# Modem_GNSS.net
KiCad netlist of a schematic drawn in Altium Designer
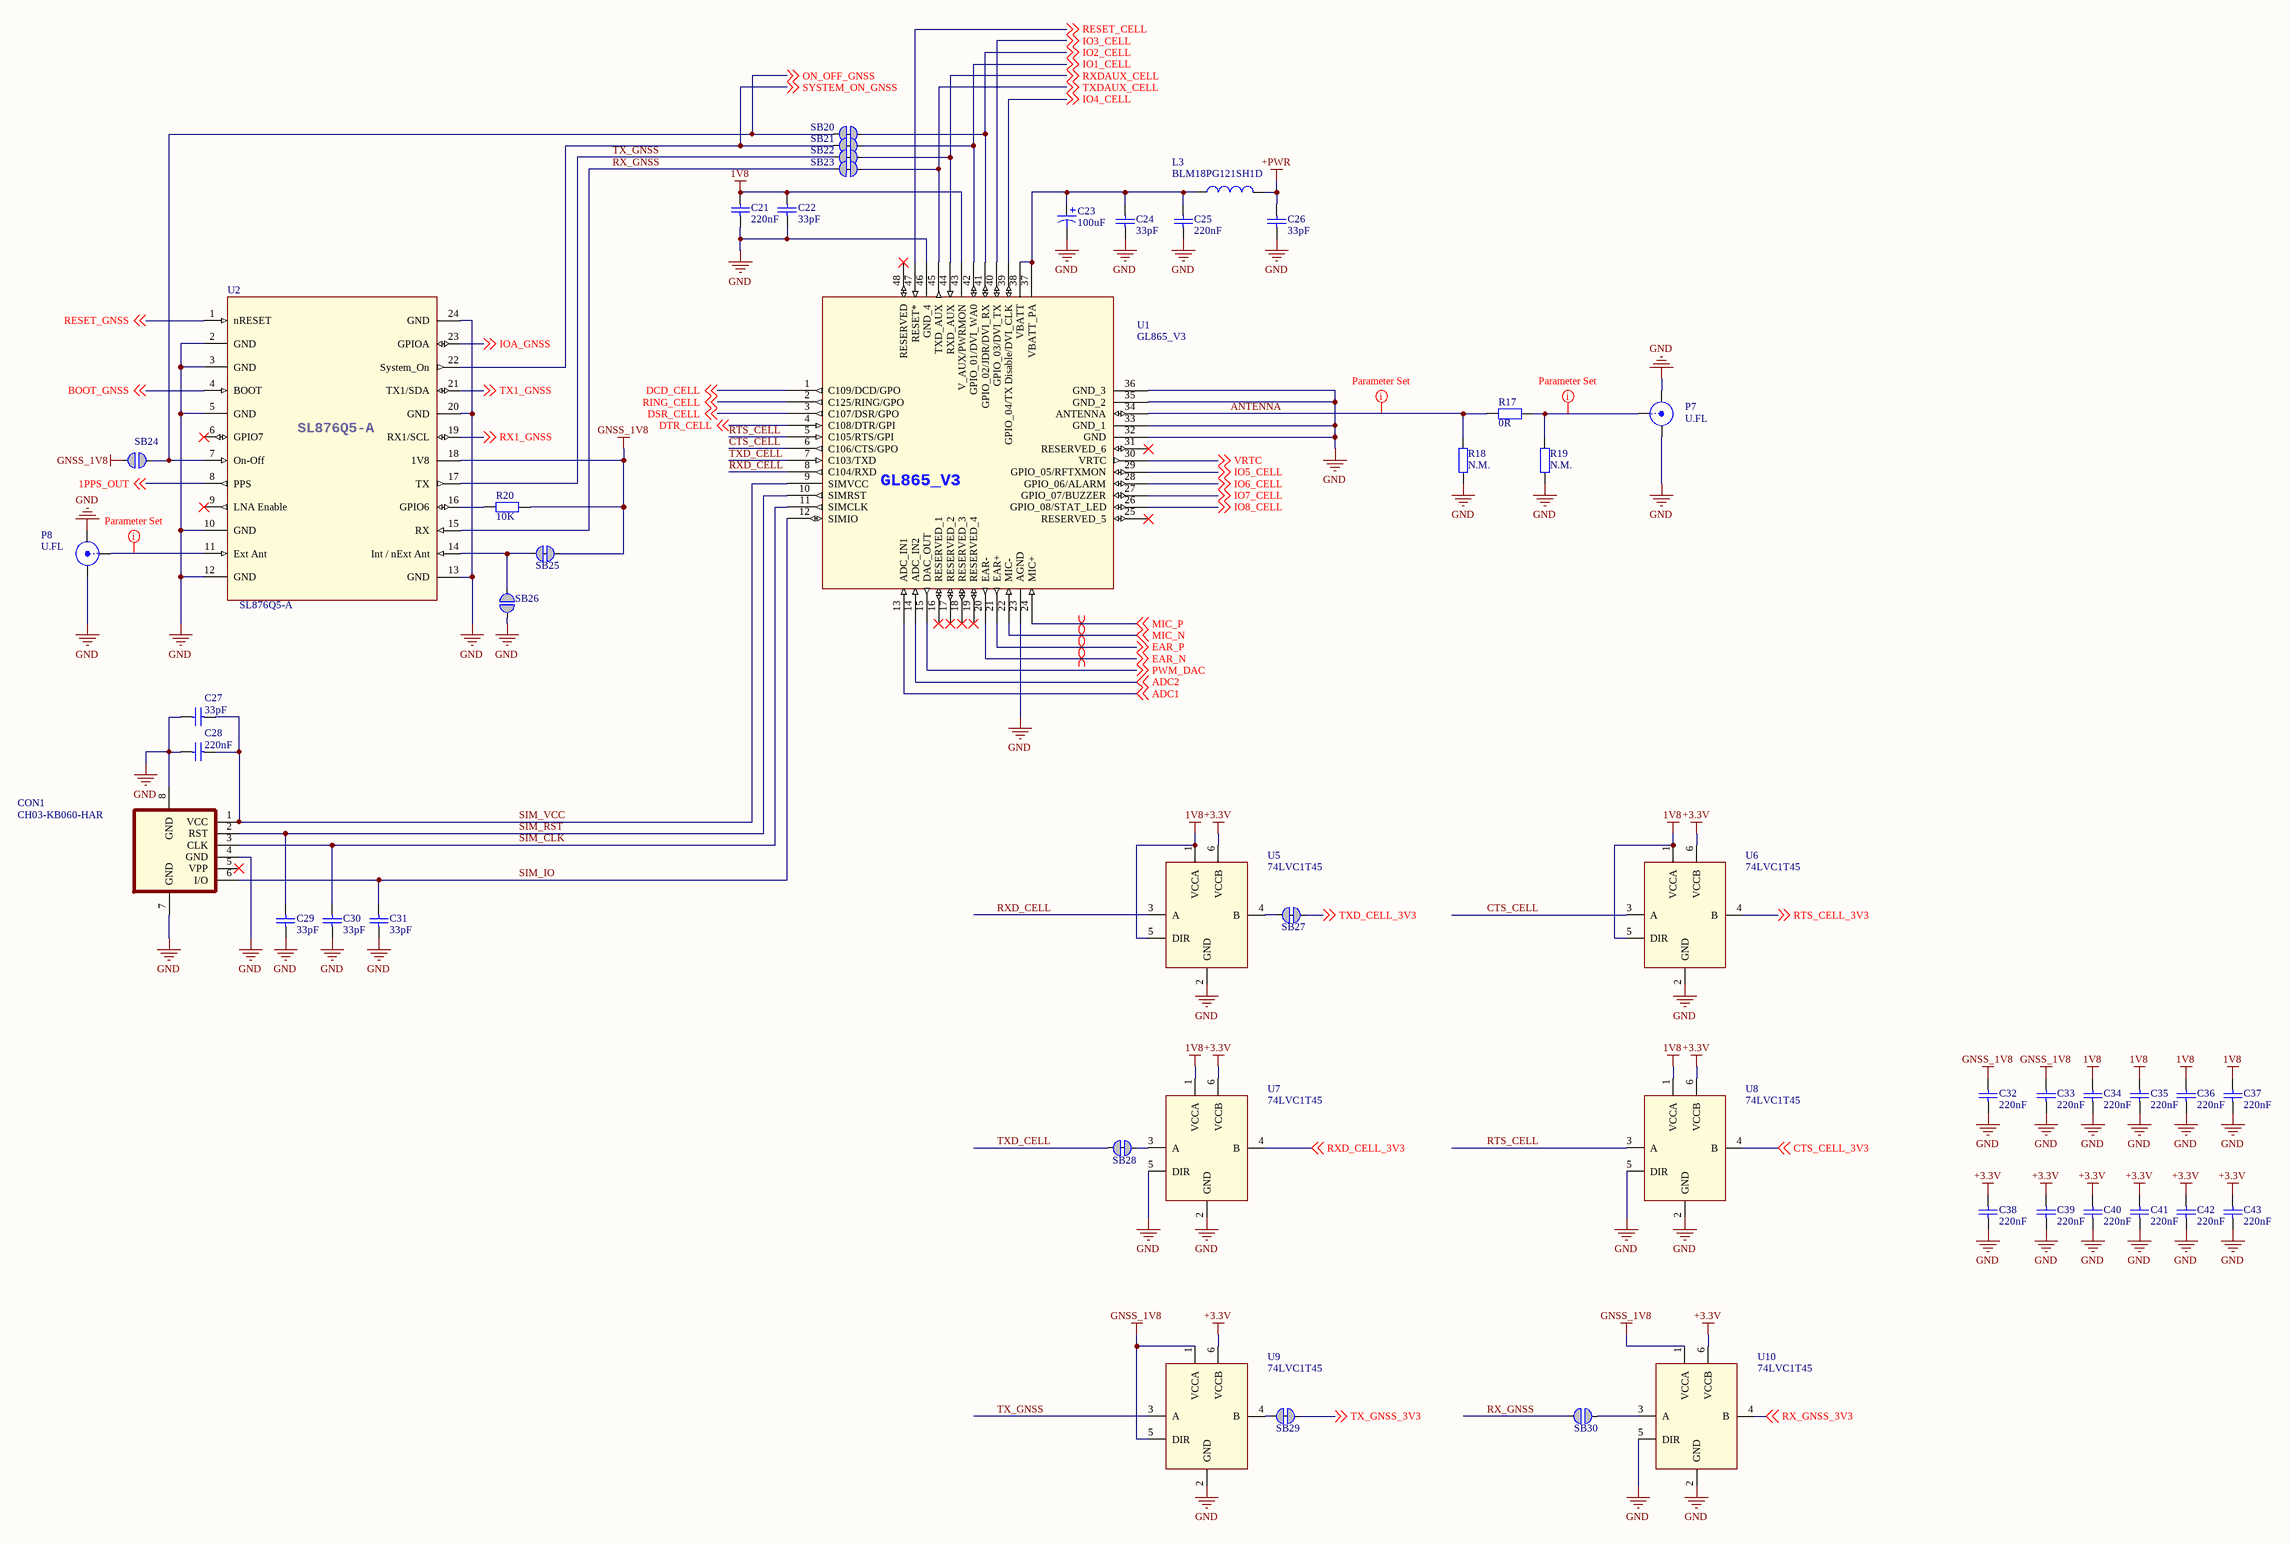
[diagram p0: Modem GNSS.SchDoc]

(export (version "E")
  (design (tool "Eeschema 10.0.6"))
  (components
    (comp (ref "C21")
      (value "220nF")
      (footprint "C0402")
      (description "Capacitor (Semiconductor SIM Model)")
      (fields
        (field (name "MANUFACTURER") "YAGEO")
        (field (name "MANUFACTURER PART NO.") "CC0402KRX5R5BB224")
      )
      (libsource (lib "Miscellaneous Devices") (part "Cap Semi"))
    )
    (comp (ref "C22")
      (value "33pF")
      (footprint "C0402")
      (description "Capacitor (Semiconductor SIM Model)")
      (fields (field (name "MANUFACTURER") "AVX") (field (name "MANUFACTURER PART NO.") "04025A330JAT2A"))
      (libsource (lib "Miscellaneous Devices") (part "Cap Semi"))
    )
    (comp (ref "C23")
      (value "100uF")
      (footprint "Case-B")
      (fields
        (field (name "MANUFACTURER") "AVX")
        (field (name "MANUFACTURER PART NO.") "TPSB107K006R0400")
        (field (name "Comment") "electrolytic capacitor")
      )
      (libsource (lib "Miscellaneous Devices") (part "Cap Pol1"))
    )
    (comp (ref "C24")
      (value "33pF")
      (footprint "C0402")
      (description "Capacitor (Semiconductor SIM Model)")
      (fields (field (name "MANUFACTURER") "AVX") (field (name "MANUFACTURER PART NO.") "04025A330JAT2A"))
      (libsource (lib "Miscellaneous Devices") (part "Cap Semi"))
    )
    (comp (ref "C25")
      (value "220nF")
      (footprint "C0402")
      (description "Capacitor (Semiconductor SIM Model)")
      (fields
        (field (name "MANUFACTURER") "YAGEO")
        (field (name "MANUFACTURER PART NO.") "CC0402KRX5R5BB224")
      )
      (libsource (lib "Miscellaneous Devices") (part "Cap Semi"))
    )
    (comp (ref "C26")
      (value "33pF")
      (footprint "C0402")
      (description "Capacitor (Semiconductor SIM Model)")
      (fields (field (name "MANUFACTURER") "AVX") (field (name "MANUFACTURER PART NO.") "04025A330JAT2A"))
      (libsource (lib "Miscellaneous Devices") (part "Cap Semi"))
    )
    (comp (ref "C27")
      (value "33pF")
      (footprint "C0402")
      (description "Capacitor (Semiconductor SIM Model)")
      (fields (field (name "MANUFACTURER") "AVX") (field (name "MANUFACTURER PART NO.") "04025A330JAT2A"))
      (libsource (lib "Miscellaneous Devices") (part "Cap Semi"))
    )
    (comp (ref "C28")
      (value "220nF")
      (footprint "C0402")
      (description "Capacitor (Semiconductor SIM Model)")
      (fields
        (field (name "MANUFACTURER") "YAGEO")
        (field (name "MANUFACTURER PART NO.") "CC0402KRX5R5BB224")
      )
      (libsource (lib "Miscellaneous Devices") (part "Cap Semi"))
    )
    (comp (ref "C29")
      (value "33pF")
      (footprint "C0402")
      (description "Capacitor (Semiconductor SIM Model)")
      (fields (field (name "MANUFACTURER") "AVX") (field (name "MANUFACTURER PART NO.") "04025A330JAT2A"))
      (libsource (lib "Miscellaneous Devices") (part "Cap Semi"))
    )
    (comp (ref "C30")
      (value "33pF")
      (footprint "C0402")
      (description "Capacitor (Semiconductor SIM Model)")
      (fields (field (name "MANUFACTURER") "AVX") (field (name "MANUFACTURER PART NO.") "04025A330JAT2A"))
      (libsource (lib "Miscellaneous Devices") (part "Cap Semi"))
    )
    (comp (ref "C31")
      (value "33pF")
      (footprint "C0402")
      (description "Capacitor (Semiconductor SIM Model)")
      (fields (field (name "MANUFACTURER") "AVX") (field (name "MANUFACTURER PART NO.") "04025A330JAT2A"))
      (libsource (lib "Miscellaneous Devices") (part "Cap Semi"))
    )
    (comp (ref "C32")
      (value "220nF")
      (footprint "C0402")
      (description "Capacitor (Semiconductor SIM Model)")
      (fields
        (field (name "MANUFACTURER") "YAGEO")
        (field (name "MANUFACTURER PART NO.") "CC0402KRX5R5BB224")
      )
      (libsource (lib "Miscellaneous Devices") (part "Cap Semi"))
    )
    (comp (ref "C33")
      (value "220nF")
      (footprint "C0402")
      (description "Capacitor (Semiconductor SIM Model)")
      (fields
        (field (name "MANUFACTURER") "YAGEO")
        (field (name "MANUFACTURER PART NO.") "CC0402KRX5R5BB224")
      )
      (libsource (lib "Miscellaneous Devices") (part "Cap Semi"))
    )
    (comp (ref "C34")
      (value "220nF")
      (footprint "C0402")
      (description "Capacitor (Semiconductor SIM Model)")
      (fields
        (field (name "MANUFACTURER") "YAGEO")
        (field (name "MANUFACTURER PART NO.") "CC0402KRX5R5BB224")
      )
      (libsource (lib "Miscellaneous Devices") (part "Cap Semi"))
    )
    (comp (ref "C35")
      (value "220nF")
      (footprint "C0402")
      (description "Capacitor (Semiconductor SIM Model)")
      (fields
        (field (name "MANUFACTURER") "YAGEO")
        (field (name "MANUFACTURER PART NO.") "CC0402KRX5R5BB224")
      )
      (libsource (lib "Miscellaneous Devices") (part "Cap Semi"))
    )
    (comp (ref "C36")
      (value "220nF")
      (footprint "C0402")
      (description "Capacitor (Semiconductor SIM Model)")
      (fields
        (field (name "MANUFACTURER") "YAGEO")
        (field (name "MANUFACTURER PART NO.") "CC0402KRX5R5BB224")
      )
      (libsource (lib "Miscellaneous Devices") (part "Cap Semi"))
    )
    (comp (ref "C37")
      (value "220nF")
      (footprint "C0402")
      (description "Capacitor (Semiconductor SIM Model)")
      (fields
        (field (name "MANUFACTURER") "YAGEO")
        (field (name "MANUFACTURER PART NO.") "CC0402KRX5R5BB224")
      )
      (libsource (lib "Miscellaneous Devices") (part "Cap Semi"))
    )
    (comp (ref "C38")
      (value "220nF")
      (footprint "C0402")
      (description "Capacitor (Semiconductor SIM Model)")
      (fields
        (field (name "MANUFACTURER") "YAGEO")
        (field (name "MANUFACTURER PART NO.") "CC0402KRX5R5BB224")
      )
      (libsource (lib "Miscellaneous Devices") (part "Cap Semi"))
    )
    (comp (ref "C39")
      (value "220nF")
      (footprint "C0402")
      (description "Capacitor (Semiconductor SIM Model)")
      (fields
        (field (name "MANUFACTURER") "YAGEO")
        (field (name "MANUFACTURER PART NO.") "CC0402KRX5R5BB224")
      )
      (libsource (lib "Miscellaneous Devices") (part "Cap Semi"))
    )
    (comp (ref "C40")
      (value "220nF")
      (footprint "C0402")
      (description "Capacitor (Semiconductor SIM Model)")
      (fields
        (field (name "MANUFACTURER") "YAGEO")
        (field (name "MANUFACTURER PART NO.") "CC0402KRX5R5BB224")
      )
      (libsource (lib "Miscellaneous Devices") (part "Cap Semi"))
    )
    (comp (ref "C41")
      (value "220nF")
      (footprint "C0402")
      (description "Capacitor (Semiconductor SIM Model)")
      (fields
        (field (name "MANUFACTURER") "YAGEO")
        (field (name "MANUFACTURER PART NO.") "CC0402KRX5R5BB224")
      )
      (libsource (lib "Miscellaneous Devices") (part "Cap Semi"))
    )
    (comp (ref "C42")
      (value "220nF")
      (footprint "C0402")
      (description "Capacitor (Semiconductor SIM Model)")
      (fields
        (field (name "MANUFACTURER") "YAGEO")
        (field (name "MANUFACTURER PART NO.") "CC0402KRX5R5BB224")
      )
      (libsource (lib "Miscellaneous Devices") (part "Cap Semi"))
    )
    (comp (ref "C43")
      (value "220nF")
      (footprint "C0402")
      (description "Capacitor (Semiconductor SIM Model)")
      (fields
        (field (name "MANUFACTURER") "YAGEO")
        (field (name "MANUFACTURER PART NO.") "CC0402KRX5R5BB224")
      )
      (libsource (lib "Miscellaneous Devices") (part "Cap Semi"))
    )
    (comp (ref "CON1")
      (value "CH03-KB060-HAR")
      (footprint "CH03-KB")
      (description "Nano SIM Card Connector")
      (fields (field (name "MANUFACTURER") "GradConn"))
      (libsource (lib "CH03-KB060-HAR") (part "CH03-KB060-HAR"))
    )
    (comp (ref "L3")
      (value "BLM18PG121SH1D")
      (footprint "L0603")
      (description "Inductor")
      (fields (field (name "MANUFACTURER") "muRata"))
      (libsource (lib "Miscellaneous Devices") (part "Inductor"))
    )
    (comp (ref "P7")
      (value "U.FL")
      (footprint "U.FL_Connector_Male")
      (fields
        (field (name "MANUFACTURER") "HIROSE")
        (field (name "MANUFACTURER PART NO.") "U.FL-R-SMT-1(10)")
      )
      (libsource (lib "RUT_L865_Project_1") (part "SMB"))
    )
    (comp (ref "P8")
      (value "U.FL")
      (footprint "U.FL_Connector_Male")
      (fields
        (field (name "MANUFACTURER") "HIROSE")
        (field (name "MANUFACTURER PART NO.") "U.FL-R-SMT-1(10)")
      )
      (libsource (lib "RUT_L865_Project_1") (part "SMB"))
    )
    (comp (ref "R17")
      (value "0R")
      (footprint "R0402")
      (fields
        (field (name "MANUFACTURER") "YAGEO")
        (field (name "MANUFACTURER PART NO.") "RC0402FR-070RL")
        (field (name "Comment") "Res2")
      )
      (libsource (lib "") (part "Res2_1"))
    )
    (comp (ref "R18")
      (value "N.M.")
      (footprint "R0402")
      (fields
        (field (name "MANUFACTURER") "YAGEO")
        (field (name "MANUFACTURER PART NO.") "RC0402FR-070RL")
        (field (name "Comment") "Res2")
      )
      (libsource (lib "") (part "Res2_2"))
    )
    (comp (ref "R19")
      (value "N.M.")
      (footprint "R0402")
      (fields
        (field (name "MANUFACTURER") "YAGEO")
        (field (name "MANUFACTURER PART NO.") "RC0402FR-070RL")
        (field (name "Comment") "Res2")
      )
      (libsource (lib "") (part "Res2_2"))
    )
    (comp (ref "R20")
      (value "10K")
      (footprint "R0402")
      (fields
        (field (name "MANUFACTURER") "ASJ")
        (field (name "MANUFACTURER PART NO.") "CR10-103-JK")
        (field (name "Comment") "Res2")
      )
      (libsource (lib "Miscellaneous Devices") (part "Res2"))
    )
    (comp (ref "SB20")
      (value "Solderbridge")
      (footprint "Solderbridge_Shorted")
      (libsource (lib "altium-import") (part "root_0_SOLDERBRIDGE_SHORTED_"))
    )
    (comp (ref "SB21")
      (value "Solderbridge")
      (footprint "Solderbridge_Shorted")
      (libsource (lib "altium-import") (part "root_0_SOLDERBRIDGE_SHORTED_"))
    )
    (comp (ref "SB22")
      (value "Solderbridge")
      (footprint "Solderbridge_Shorted")
      (libsource (lib "altium-import") (part "root_0_SOLDERBRIDGE_SHORTED_"))
    )
    (comp (ref "SB23")
      (value "Solderbridge")
      (footprint "Solderbridge_Shorted")
      (libsource (lib "altium-import") (part "root_0_SOLDERBRIDGE_SHORTED_"))
    )
    (comp (ref "SB24")
      (value "Solderbridge")
      (footprint "Solderbridge")
      (libsource (lib "altium-import") (part "root_0_SOLDERBRIDGE_"))
    )
    (comp (ref "SB25")
      (value "Solderbridge")
      (footprint "Solderbridge_Shorted")
      (libsource (lib "altium-import") (part "root_0_SOLDERBRIDGE_SHORTED_"))
    )
    (comp (ref "SB26")
      (value "Solderbridge")
      (footprint "Solderbridge")
      (libsource (lib "altium-import") (part "root_3_SOLDERBRIDGE_"))
    )
    (comp (ref "SB27")
      (value "Solderbridge")
      (footprint "Solderbridge_Shorted")
      (libsource (lib "altium-import") (part "root_0_SOLDERBRIDGE_SHORTED_"))
    )
    (comp (ref "SB28")
      (value "Solderbridge")
      (footprint "Solderbridge_Shorted")
      (libsource (lib "altium-import") (part "root_2_SOLDERBRIDGE_SHORTED_"))
    )
    (comp (ref "SB29")
      (value "Solderbridge")
      (footprint "Solderbridge_Shorted")
      (libsource (lib "altium-import") (part "root_2_SOLDERBRIDGE_SHORTED_"))
    )
    (comp (ref "SB30")
      (value "Solderbridge")
      (footprint "Solderbridge")
      (libsource (lib "altium-import") (part "root_0_SOLDERBRIDGE_"))
    )
    (comp (ref "U1")
      (value "GL865_V3")
      (footprint "XL865XXX")
      (fields (field (name "MANUFACTURER") "Telit") (field (name "MANUFACTURER PART NO.") "GL865-DUAL V3.1"))
      (libsource (lib "RUT_L865_Project_1") (part "GL865_V3"))
    )
    (comp (ref "U2")
      (value "SL876Q5-A")
      (footprint "SL876Q5-A")
      (fields (field (name "MANUFACTURER") "Telit"))
      (libsource (lib "SL876-Q5A") (part "SL876Q5-A"))
    )
    (comp (ref "U5")
      (value "74LVC1T45")
      (footprint "X2-DFN1410-6")
      (fields
        (field (name "MANUFACTURER") "Diodes Inc.")
        (field (name "MANUFACTURER PART NO.") "74LVC1T45FZ4-7")
      )
      (libsource (lib "74LVC1T45") (part "74LVC1T45"))
    )
    (comp (ref "U6")
      (value "74LVC1T45")
      (footprint "X2-DFN1410-6")
      (fields
        (field (name "MANUFACTURER") "Diodes Inc.")
        (field (name "MANUFACTURER PART NO.") "74LVC1T45FZ4-7")
      )
      (libsource (lib "74LVC1T45") (part "74LVC1T45"))
    )
    (comp (ref "U7")
      (value "74LVC1T45")
      (footprint "X2-DFN1410-6")
      (fields
        (field (name "MANUFACTURER") "Diodes Inc.")
        (field (name "MANUFACTURER PART NO.") "74LVC1T45FZ4-7")
      )
      (libsource (lib "74LVC1T45") (part "74LVC1T45"))
    )
    (comp (ref "U8")
      (value "74LVC1T45")
      (footprint "X2-DFN1410-6")
      (fields
        (field (name "MANUFACTURER") "Diodes Inc.")
        (field (name "MANUFACTURER PART NO.") "74LVC1T45FZ4-7")
      )
      (libsource (lib "74LVC1T45") (part "74LVC1T45"))
    )
    (comp (ref "U9")
      (value "74LVC1T45")
      (footprint "X2-DFN1410-6")
      (fields
        (field (name "MANUFACTURER") "Diodes Inc.")
        (field (name "MANUFACTURER PART NO.") "74LVC1T45FZ4-7")
      )
      (libsource (lib "74LVC1T45") (part "74LVC1T45"))
    )
    (comp (ref "U10")
      (value "74LVC1T45")
      (footprint "X2-DFN1410-6")
      (fields
        (field (name "MANUFACTURER") "Diodes Inc.")
        (field (name "MANUFACTURER PART NO.") "74LVC1T45FZ4-7")
      )
      (libsource (lib "74LVC1T45") (part "74LVC1T45"))
    )
  )
  (nets
    (net (code "1") (name "+3.3V") (class "Default")
      (node (ref "C38") (pin "1") (pinfunction "1_1") (pintype "passive"))
      (node (ref "C39") (pin "1") (pinfunction "1_1") (pintype "passive"))
      (node (ref "C40") (pin "1") (pinfunction "1_1") (pintype "passive"))
      (node (ref "C41") (pin "1") (pinfunction "1_1") (pintype "passive"))
      (node (ref "C42") (pin "1") (pinfunction "1_1") (pintype "passive"))
      (node (ref "C43") (pin "1") (pinfunction "1_1") (pintype "passive"))
      (node (ref "U10") (pin "6") (pinfunction "VCCB_6") (pintype "passive"))
      (node (ref "U5") (pin "6") (pinfunction "VCCB_6") (pintype "passive"))
      (node (ref "U6") (pin "6") (pinfunction "VCCB_6") (pintype "passive"))
      (node (ref "U7") (pin "6") (pinfunction "VCCB_6") (pintype "passive"))
      (node (ref "U8") (pin "6") (pinfunction "VCCB_6") (pintype "passive"))
      (node (ref "U9") (pin "6") (pinfunction "VCCB_6") (pintype "passive"))
    )
    (net (code "2") (name "+PWR") (class "Default")
      (node (ref "C26") (pin "2") (pinfunction "2_2") (pintype "passive"))
      (node (ref "L3") (pin "2") (pinfunction "2_2") (pintype "passive"))
    )
    (net (code "3") (name "/ANTENNA") (class "Default")
      (node (ref "R17") (pin "2") (pinfunction "2_2") (pintype "passive"))
      (node (ref "R18") (pin "1") (pinfunction "1_1") (pintype "passive"))
      (node (ref "U1") (pin "34") (pinfunction "ANTENNA_34") (pintype "bidirectional"))
    )
    (net (code "4") (name "/CTS_CELL") (class "Default")
      (node (ref "U1") (pin "6") (pinfunction "C106/CTS/GPO_6") (pintype "output"))
      (node (ref "U6") (pin "3") (pinfunction "A_3") (pintype "passive"))
    )
    (net (code "5") (name "/RTS_CELL") (class "Default")
      (node (ref "U1") (pin "5") (pinfunction "C105/RTS/GPI_5") (pintype "input"))
      (node (ref "U8") (pin "3") (pinfunction "A_3") (pintype "passive"))
    )
    (net (code "6") (name "/RXD_CELL") (class "Default")
      (node (ref "U1") (pin "8") (pinfunction "C104/RXD_8") (pintype "output"))
      (node (ref "U5") (pin "3") (pinfunction "A_3") (pintype "passive"))
    )
    (net (code "7") (name "/RX_GNSS") (class "Default")
      (node (ref "SB23") (pin "2") (pinfunction "1_2") (pintype "passive"))
      (node (ref "SB30") (pin "2") (pinfunction "1_2") (pintype "passive"))
      (node (ref "U2") (pin "15") (pinfunction "RX_15") (pintype "input"))
    )
    (net (code "8") (name "/SIM_CLK") (class "Default")
      (node (ref "C30") (pin "1") (pinfunction "1_1") (pintype "passive"))
      (node (ref "CON1") (pin "3") (pinfunction "CLK_3") (pintype "passive"))
      (node (ref "U1") (pin "11") (pinfunction "SIMCLK_11") (pintype "output"))
    )
    (net (code "9") (name "/SIM_IO") (class "Default")
      (node (ref "C31") (pin "1") (pinfunction "1_1") (pintype "passive"))
      (node (ref "CON1") (pin "6") (pinfunction "I/O_6") (pintype "passive"))
      (node (ref "U1") (pin "12") (pinfunction "SIMIO_12") (pintype "bidirectional"))
    )
    (net (code "10") (name "/SIM_RST") (class "Default")
      (node (ref "C29") (pin "1") (pinfunction "1_1") (pintype "passive"))
      (node (ref "CON1") (pin "2") (pinfunction "RST_2") (pintype "passive"))
      (node (ref "U1") (pin "10") (pinfunction "SIMRST_10") (pintype "output"))
    )
    (net (code "11") (name "/SIM_VCC") (class "Default")
      (node (ref "C27") (pin "1") (pinfunction "1_1") (pintype "passive"))
      (node (ref "C28") (pin "1") (pinfunction "1_1") (pintype "passive"))
      (node (ref "CON1") (pin "1") (pinfunction "VCC_1") (pintype "passive"))
      (node (ref "U1") (pin "9") (pinfunction "SIMVCC_9") (pintype "power_in"))
    )
    (net (code "12") (name "/TXD_CELL") (class "Default")
      (node (ref "SB28") (pin "1") (pinfunction "0_1") (pintype "passive"))
      (node (ref "U1") (pin "7") (pinfunction "C103/TXD_7") (pintype "input"))
    )
    (net (code "13") (name "/TX_GNSS") (class "Default")
      (node (ref "SB22") (pin "2") (pinfunction "1_2") (pintype "passive"))
      (node (ref "U2") (pin "17") (pinfunction "TX_17") (pintype "output"))
      (node (ref "U9") (pin "3") (pinfunction "A_3") (pintype "passive"))
    )
    (net (code "14") (name "1PPS_OUT") (class "Default")
      (node (ref "U2") (pin "8") (pinfunction "PPS_8") (pintype "output"))
    )
    (net (code "15") (name "1V8") (class "Default")
      (node (ref "C21") (pin "2") (pinfunction "2_2") (pintype "passive"))
      (node (ref "C22") (pin "2") (pinfunction "2_2") (pintype "passive"))
      (node (ref "C34") (pin "1") (pinfunction "1_1") (pintype "passive"))
      (node (ref "C35") (pin "1") (pinfunction "1_1") (pintype "passive"))
      (node (ref "C36") (pin "1") (pinfunction "1_1") (pintype "passive"))
      (node (ref "C37") (pin "1") (pinfunction "1_1") (pintype "passive"))
      (node (ref "U1") (pin "43") (pinfunction "V_AUX/PWRMON_43") (pintype "power_in"))
      (node (ref "U5") (pin "1") (pinfunction "VCCA_1") (pintype "passive"))
      (node (ref "U5") (pin "5") (pinfunction "DIR_5") (pintype "passive"))
      (node (ref "U6") (pin "1") (pinfunction "VCCA_1") (pintype "passive"))
      (node (ref "U6") (pin "5") (pinfunction "DIR_5") (pintype "passive"))
      (node (ref "U7") (pin "1") (pinfunction "VCCA_1") (pintype "passive"))
      (node (ref "U8") (pin "1") (pinfunction "VCCA_1") (pintype "passive"))
    )
    (net (code "16") (name "ADC1") (class "Default")
      (node (ref "U1") (pin "13") (pinfunction "ADC_IN1_13") (pintype "input"))
    )
    (net (code "17") (name "ADC2") (class "Default")
      (node (ref "U1") (pin "14") (pinfunction "ADC_IN2_14") (pintype "input"))
    )
    (net (code "18") (name "BOOT_GNSS") (class "Default")
      (node (ref "U2") (pin "4") (pinfunction "BOOT_4") (pintype "input"))
    )
    (net (code "19") (name "CTS_CELL_3V3") (class "Default")
      (node (ref "U8") (pin "4") (pinfunction "B_4") (pintype "passive"))
    )
    (net (code "20") (name "DCD_CELL") (class "Default")
      (node (ref "U1") (pin "1") (pinfunction "C109/DCD/GPO_1") (pintype "output"))
    )
    (net (code "21") (name "DSR_CELL") (class "Default")
      (node (ref "U1") (pin "3") (pinfunction "C107/DSR/GPO_3") (pintype "output"))
    )
    (net (code "22") (name "DTR_CELL") (class "Default")
      (node (ref "U1") (pin "4") (pinfunction "C108/DTR/GPI_4") (pintype "input"))
    )
    (net (code "23") (name "EAR_N") (class "Default")
      (node (ref "U1") (pin "20") (pinfunction "EAR-_20") (pintype "output"))
    )
    (net (code "24") (name "EAR_P") (class "Default")
      (node (ref "U1") (pin "21") (pinfunction "EAR+_21") (pintype "output"))
    )
    (net (code "25") (name "GND") (class "Default")
      (node (ref "C21") (pin "1") (pinfunction "1_1") (pintype "passive"))
      (node (ref "C22") (pin "1") (pinfunction "1_1") (pintype "passive"))
      (node (ref "C23") (pin "2") (pinfunction "2_2") (pintype "passive"))
      (node (ref "C24") (pin "1") (pinfunction "1_1") (pintype "passive"))
      (node (ref "C25") (pin "1") (pinfunction "1_1") (pintype "passive"))
      (node (ref "C26") (pin "1") (pinfunction "1_1") (pintype "passive"))
      (node (ref "C27") (pin "2") (pinfunction "2_2") (pintype "passive"))
      (node (ref "C28") (pin "2") (pinfunction "2_2") (pintype "passive"))
      (node (ref "C29") (pin "2") (pinfunction "2_2") (pintype "passive"))
      (node (ref "C30") (pin "2") (pinfunction "2_2") (pintype "passive"))
      (node (ref "C31") (pin "2") (pinfunction "2_2") (pintype "passive"))
      (node (ref "C32") (pin "2") (pinfunction "2_2") (pintype "passive"))
      (node (ref "C33") (pin "2") (pinfunction "2_2") (pintype "passive"))
      (node (ref "C34") (pin "2") (pinfunction "2_2") (pintype "passive"))
      (node (ref "C35") (pin "2") (pinfunction "2_2") (pintype "passive"))
      (node (ref "C36") (pin "2") (pinfunction "2_2") (pintype "passive"))
      (node (ref "C37") (pin "2") (pinfunction "2_2") (pintype "passive"))
      (node (ref "C38") (pin "2") (pinfunction "2_2") (pintype "passive"))
      (node (ref "C39") (pin "2") (pinfunction "2_2") (pintype "passive"))
      (node (ref "C40") (pin "2") (pinfunction "2_2") (pintype "passive"))
      (node (ref "C41") (pin "2") (pinfunction "2_2") (pintype "passive"))
      (node (ref "C42") (pin "2") (pinfunction "2_2") (pintype "passive"))
      (node (ref "C43") (pin "2") (pinfunction "2_2") (pintype "passive"))
      (node (ref "CON1") (pin "4") (pinfunction "GND_4") (pintype "passive"))
      (node (ref "CON1") (pin "7") (pinfunction "GND_7") (pintype "passive"))
      (node (ref "CON1") (pin "8") (pinfunction "GND_8") (pintype "passive"))
      (node (ref "P7") (pin "2") (pinfunction "Y_2") (pintype "passive"))
      (node (ref "P7") (pin "3") (pinfunction "Y_3") (pintype "passive"))
      (node (ref "P8") (pin "2") (pinfunction "Y_2") (pintype "passive"))
      (node (ref "P8") (pin "3") (pinfunction "Y_3") (pintype "passive"))
      (node (ref "R18") (pin "2") (pinfunction "2_2") (pintype "passive"))
      (node (ref "R19") (pin "2") (pinfunction "2_2") (pintype "passive"))
      (node (ref "SB26") (pin "1") (pinfunction "0_1") (pintype "passive"))
      (node (ref "U1") (pin "23") (pinfunction "AGND_23") (pintype "power_in"))
      (node (ref "U1") (pin "32") (pinfunction "GND_32") (pintype "power_in"))
      (node (ref "U1") (pin "33") (pinfunction "GND_1_33") (pintype "power_in"))
      (node (ref "U1") (pin "35") (pinfunction "GND_2_35") (pintype "power_in"))
      (node (ref "U1") (pin "36") (pinfunction "GND_3_36") (pintype "power_in"))
      (node (ref "U1") (pin "46") (pinfunction "GND_4_46") (pintype "power_in"))
      (node (ref "U10") (pin "2") (pinfunction "GND_2") (pintype "passive"))
      (node (ref "U10") (pin "5") (pinfunction "DIR_5") (pintype "passive"))
      (node (ref "U2") (pin "10") (pinfunction "GND_10") (pintype "power_in"))
      (node (ref "U2") (pin "12") (pinfunction "GND_12") (pintype "power_in"))
      (node (ref "U2") (pin "13") (pinfunction "GND_13") (pintype "power_in"))
      (node (ref "U2") (pin "2") (pinfunction "GND_2") (pintype "power_in"))
      (node (ref "U2") (pin "20") (pinfunction "GND_20") (pintype "power_in"))
      (node (ref "U2") (pin "24") (pinfunction "GND_24") (pintype "power_in"))
      (node (ref "U2") (pin "3") (pinfunction "GND_3") (pintype "power_in"))
      (node (ref "U2") (pin "5") (pinfunction "GND_5") (pintype "power_in"))
      (node (ref "U5") (pin "2") (pinfunction "GND_2") (pintype "passive"))
      (node (ref "U6") (pin "2") (pinfunction "GND_2") (pintype "passive"))
      (node (ref "U7") (pin "2") (pinfunction "GND_2") (pintype "passive"))
      (node (ref "U7") (pin "5") (pinfunction "DIR_5") (pintype "passive"))
      (node (ref "U8") (pin "2") (pinfunction "GND_2") (pintype "passive"))
      (node (ref "U8") (pin "5") (pinfunction "DIR_5") (pintype "passive"))
      (node (ref "U9") (pin "2") (pinfunction "GND_2") (pintype "passive"))
    )
    (net (code "26") (name "GNSS_1V8") (class "Default")
      (node (ref "C32") (pin "1") (pinfunction "1_1") (pintype "passive"))
      (node (ref "C33") (pin "1") (pinfunction "1_1") (pintype "passive"))
      (node (ref "R20") (pin "2") (pinfunction "2_2") (pintype "passive"))
      (node (ref "SB24") (pin "2") (pinfunction "1_2") (pintype "passive"))
      (node (ref "SB25") (pin "1") (pinfunction "0_1") (pintype "passive"))
      (node (ref "U10") (pin "1") (pinfunction "VCCA_1") (pintype "passive"))
      (node (ref "U2") (pin "18") (pinfunction "1V8_18") (pintype "power_in"))
      (node (ref "U9") (pin "1") (pinfunction "VCCA_1") (pintype "passive"))
      (node (ref "U9") (pin "5") (pinfunction "DIR_5") (pintype "passive"))
    )
    (net (code "27") (name "IO1_CELL") (class "Default")
      (node (ref "SB21") (pin "1") (pinfunction "0_1") (pintype "passive"))
      (node (ref "U1") (pin "42") (pinfunction "GPIO_01/DVI_WA0_42") (pintype "bidirectional"))
    )
    (net (code "28") (name "IO2_CELL") (class "Default")
      (node (ref "SB20") (pin "1") (pinfunction "0_1") (pintype "passive"))
      (node (ref "U1") (pin "41") (pinfunction "GPIO_02/JDR/DVI_RX_41") (pintype "bidirectional"))
    )
    (net (code "29") (name "IO3_CELL") (class "Default")
      (node (ref "U1") (pin "40") (pinfunction "GPIO_03/DVI_TX_40") (pintype "bidirectional"))
    )
    (net (code "30") (name "IO4_CELL") (class "Default")
      (node (ref "U1") (pin "39") (pinfunction "GPIO_04/TX_Disable/DVI_CLK_39") (pintype "bidirectional"))
    )
    (net (code "31") (name "IO5_CELL") (class "Default")
      (node (ref "U1") (pin "29") (pinfunction "GPIO_05/RFTXMON_29") (pintype "bidirectional"))
    )
    (net (code "32") (name "IO6_CELL") (class "Default")
      (node (ref "U1") (pin "28") (pinfunction "GPIO_06/ALARM_28") (pintype "bidirectional"))
    )
    (net (code "33") (name "IO7_CELL") (class "Default")
      (node (ref "U1") (pin "27") (pinfunction "GPIO_07/BUZZER_27") (pintype "bidirectional"))
    )
    (net (code "34") (name "IO8_CELL") (class "Default")
      (node (ref "U1") (pin "26") (pinfunction "GPIO_08/STAT_LED_26") (pintype "bidirectional"))
    )
    (net (code "35") (name "IOA_GNSS") (class "Default")
      (node (ref "U2") (pin "23") (pinfunction "GPIOA_23") (pintype "bidirectional"))
    )
    (net (code "36") (name "MIC_N") (class "Default")
      (node (ref "U1") (pin "22") (pinfunction "MIC-_22") (pintype "input"))
    )
    (net (code "37") (name "MIC_P") (class "Default")
      (node (ref "U1") (pin "24") (pinfunction "MIC+_24") (pintype "input"))
    )
    (net (code "38") (name "Net-(P7-X)") (class "Default")
      (node (ref "P7") (pin "1") (pinfunction "X_1") (pintype "passive"))
      (node (ref "R17") (pin "1") (pinfunction "1_1") (pintype "passive"))
      (node (ref "R19") (pin "1") (pinfunction "1_1") (pintype "passive"))
    )
    (net (code "39") (name "Net-(P8-X)") (class "Default")
      (node (ref "P8") (pin "1") (pinfunction "X_1") (pintype "passive"))
      (node (ref "U2") (pin "11") (pinfunction "Ext_Ant_11") (pintype "input"))
    )
    (net (code "40") (name "Net-(SB25-1)") (class "Default")
      (node (ref "SB25") (pin "2") (pinfunction "1_2") (pintype "passive"))
      (node (ref "SB26") (pin "2") (pinfunction "1_2") (pintype "passive"))
      (node (ref "U2") (pin "14") (pinfunction "Int_/_nExt_Ant_14") (pintype "input"))
    )
    (net (code "41") (name "Net-(SB27-1)") (class "Default")
      (node (ref "SB27") (pin "2") (pinfunction "1_2") (pintype "passive"))
      (node (ref "U5") (pin "4") (pinfunction "B_4") (pintype "passive"))
    )
    (net (code "42") (name "Net-(SB28-1)") (class "Default")
      (node (ref "SB28") (pin "2") (pinfunction "1_2") (pintype "passive"))
      (node (ref "U7") (pin "3") (pinfunction "A_3") (pintype "passive"))
    )
    (net (code "43") (name "Net-(SB29-0)") (class "Default")
      (node (ref "SB29") (pin "1") (pinfunction "0_1") (pintype "passive"))
      (node (ref "U9") (pin "4") (pinfunction "B_4") (pintype "passive"))
    )
    (net (code "44") (name "Net-(SB30-0)") (class "Default")
      (node (ref "SB30") (pin "1") (pinfunction "0_1") (pintype "passive"))
      (node (ref "U10") (pin "3") (pinfunction "A_3") (pintype "passive"))
    )
    (net (code "45") (name "Net-(U1-VBATT)") (class "Default")
      (node (ref "C23") (pin "1") (pinfunction "1_1") (pintype "passive"))
      (node (ref "C24") (pin "2") (pinfunction "2_2") (pintype "passive"))
      (node (ref "C25") (pin "2") (pinfunction "2_2") (pintype "passive"))
      (node (ref "L3") (pin "1") (pinfunction "1_1") (pintype "passive"))
      (node (ref "U1") (pin "37") (pinfunction "VBATT_PA_37") (pintype "power_in"))
      (node (ref "U1") (pin "38") (pinfunction "VBATT_38") (pintype "power_in"))
    )
    (net (code "46") (name "Net-(U2-GPIO6)") (class "Default")
      (node (ref "R20") (pin "1") (pinfunction "1_1") (pintype "passive"))
      (node (ref "U2") (pin "16") (pinfunction "GPIO6_16") (pintype "bidirectional"))
    )
    (net (code "47") (name "ON_OFF_GNSS") (class "Default")
      (node (ref "SB20") (pin "2") (pinfunction "1_2") (pintype "passive"))
      (node (ref "SB24") (pin "1") (pinfunction "0_1") (pintype "passive"))
      (node (ref "U2") (pin "7") (pinfunction "On-Off_7") (pintype "input"))
    )
    (net (code "48") (name "PWM_DAC") (class "Default")
      (node (ref "U1") (pin "15") (pinfunction "DAC_OUT_15") (pintype "output"))
    )
    (net (code "49") (name "RESET_CELL") (class "Default")
      (node (ref "U1") (pin "47") (pinfunction "RESET*_47") (pintype "input"))
    )
    (net (code "50") (name "RESET_GNSS") (class "Default")
      (node (ref "U2") (pin "1") (pinfunction "nRESET_1") (pintype "input"))
    )
    (net (code "51") (name "RING_CELL") (class "Default")
      (node (ref "U1") (pin "2") (pinfunction "C125/RING/GPO_2") (pintype "output"))
    )
    (net (code "52") (name "RTS_CELL_3V3") (class "Default")
      (node (ref "U6") (pin "4") (pinfunction "B_4") (pintype "passive"))
    )
    (net (code "53") (name "RX1_GNSS") (class "Default")
      (node (ref "U2") (pin "19") (pinfunction "RX1/SCL_19") (pintype "bidirectional"))
    )
    (net (code "54") (name "RXDAUX_CELL") (class "Default")
      (node (ref "SB22") (pin "1") (pinfunction "0_1") (pintype "passive"))
      (node (ref "U1") (pin "44") (pinfunction "RXD_AUX_44") (pintype "input"))
    )
    (net (code "55") (name "RXD_CELL_3V3") (class "Default")
      (node (ref "U7") (pin "4") (pinfunction "B_4") (pintype "passive"))
    )
    (net (code "56") (name "RX_GNSS_3V3") (class "Default")
      (node (ref "U10") (pin "4") (pinfunction "B_4") (pintype "passive"))
    )
    (net (code "57") (name "SYSTEM_ON_GNSS") (class "Default")
      (node (ref "SB21") (pin "2") (pinfunction "1_2") (pintype "passive"))
      (node (ref "U2") (pin "22") (pinfunction "System_On_22") (pintype "output"))
    )
    (net (code "58") (name "TX1_GNSS") (class "Default")
      (node (ref "U2") (pin "21") (pinfunction "TX1/SDA_21") (pintype "bidirectional"))
    )
    (net (code "59") (name "TXDAUX_CELL") (class "Default")
      (node (ref "SB23") (pin "1") (pinfunction "0_1") (pintype "passive"))
      (node (ref "U1") (pin "45") (pinfunction "TXD_AUX_45") (pintype "output"))
    )
    (net (code "60") (name "TXD_CELL_3V3") (class "Default")
      (node (ref "SB27") (pin "1") (pinfunction "0_1") (pintype "passive"))
    )
    (net (code "61") (name "TX_GNSS_3V3") (class "Default")
      (node (ref "SB29") (pin "2") (pinfunction "1_2") (pintype "passive"))
    )
    (net (code "62") (name "VRTC") (class "Default")
      (node (ref "U1") (pin "30") (pinfunction "VRTC_30") (pintype "output"))
    )
    (net (code "63") (name "unconnected-(CON1-VPP-Pad5)") (class "Default")
      (node (ref "CON1") (pin "5") (pinfunction "VPP_5") (pintype "passive+no_connect"))
    )
    (net (code "64") (name "unconnected-(U1-RESERVED-Pad48)") (class "Default")
      (node (ref "U1") (pin "48") (pinfunction "RESERVED_48") (pintype "bidirectional+no_connect"))
    )
    (net (code "65") (name "unconnected-(U1-RESERVED_1-Pad16)") (class "Default")
      (node (ref "U1") (pin "16") (pinfunction "RESERVED_1_16") (pintype "bidirectional+no_connect"))
    )
    (net (code "66") (name "unconnected-(U1-RESERVED_2-Pad17)") (class "Default")
      (node (ref "U1") (pin "17") (pinfunction "RESERVED_2_17") (pintype "bidirectional+no_connect"))
    )
    (net (code "67") (name "unconnected-(U1-RESERVED_3-Pad18)") (class "Default")
      (node (ref "U1") (pin "18") (pinfunction "RESERVED_3_18") (pintype "bidirectional+no_connect"))
    )
    (net (code "68") (name "unconnected-(U1-RESERVED_4-Pad19)") (class "Default")
      (node (ref "U1") (pin "19") (pinfunction "RESERVED_4_19") (pintype "bidirectional+no_connect"))
    )
    (net (code "69") (name "unconnected-(U1-RESERVED_5-Pad25)") (class "Default")
      (node (ref "U1") (pin "25") (pinfunction "RESERVED_5_25") (pintype "bidirectional+no_connect"))
    )
    (net (code "70") (name "unconnected-(U1-RESERVED_6-Pad31)") (class "Default")
      (node (ref "U1") (pin "31") (pinfunction "RESERVED_6_31") (pintype "bidirectional+no_connect"))
    )
    (net (code "71") (name "unconnected-(U2-GPIO7-Pad6)") (class "Default")
      (node (ref "U2") (pin "6") (pinfunction "GPIO7_6") (pintype "bidirectional+no_connect"))
    )
    (net (code "72") (name "unconnected-(U2-LNA_Enable-Pad9)") (class "Default")
      (node (ref "U2") (pin "9") (pinfunction "LNA_Enable_9") (pintype "output+no_connect"))
    )
  )
)
